# Ni-MH-charger-module.net
KiCad netlist of a schematic drawn in EAGLE
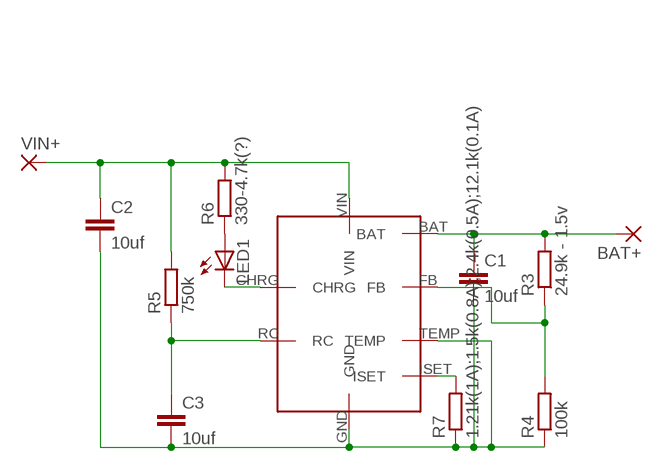
[diagram p0: schematic, sheet 1]

(export (version "E")
  (design (tool "Eeschema 10.0.6"))
  (components
    (comp (ref "BAT+")
      (value "SMD5")
      (footprint "eagle-import:SMD2,54-5,08")
      (libsource (lib "eagle-import") (part "SMD5"))
    )
    (comp (ref "C1")
      (value "10uf")
      (footprint "eagle-import:C0805")
      (libsource (lib "eagle-import") (part "C-EUC0805"))
    )
    (comp (ref "C2")
      (value "10uf")
      (footprint "eagle-import:C0805")
      (libsource (lib "eagle-import") (part "C-EUC0805"))
    )
    (comp (ref "C3")
      (value "10uf")
      (footprint "eagle-import:C0805")
      (libsource (lib "eagle-import") (part "C-EUC0805"))
    )
    (comp (ref "LED1")
      (value "LEDCHIPLED_0805")
      (footprint "eagle-import:CHIPLED_0805")
      (libsource (lib "eagle-import") (part "LEDCHIPLED_0805"))
    )
    (comp (ref "R3")
      (value "24.9k - 1.5v")
      (footprint "eagle-import:R0805")
      (libsource (lib "eagle-import") (part "R-EU_R0805"))
    )
    (comp (ref "R4")
      (value "100k")
      (footprint "eagle-import:R0805")
      (libsource (lib "eagle-import") (part "R-EU_R0805"))
    )
    (comp (ref "R5")
      (value "750k")
      (footprint "eagle-import:R0805")
      (libsource (lib "eagle-import") (part "R-EU_R0805"))
    )
    (comp (ref "R6")
      (value "330-4.7k(?)")
      (footprint "eagle-import:R0805")
      (libsource (lib "eagle-import") (part "R-EU_R0805"))
    )
    (comp (ref "R7")
      (value "1.21k(1A);1.5k(0.8A);2.4k(0.5A);12.1k(0.1A)")
      (footprint "eagle-import:R0805")
      (libsource (lib "eagle-import") (part "R-EU_R0805"))
    )
    (comp (ref "U$1")
      (value "CN3085")
      (footprint "eagle-import:CN3085")
      (libsource (lib "eagle-import") (part "CN3085"))
    )
    (comp (ref "VIN+")
      (value "SMD5")
      (footprint "eagle-import:SMD2,54-5,08")
      (libsource (lib "eagle-import") (part "SMD5"))
    )
  )
  (nets
    (net (code "1") (name "Net-(BAT+-P)") (class "Default")
      (node (ref "BAT+") (pin "1") (pinfunction "P_1") (pintype "passive"))
      (node (ref "C1") (pin "1") (pinfunction "1_1") (pintype "passive"))
      (node (ref "R3") (pin "2") (pinfunction "2_2") (pintype "passive"))
      (node (ref "U$1") (pin "BAT") (pinfunction "BAT_BAT") (pintype "bidirectional"))
    )
    (net (code "2") (name "Net-(C1-Pad2)") (class "Default")
      (node (ref "C1") (pin "2") (pinfunction "2_2") (pintype "passive"))
      (node (ref "C2") (pin "2") (pinfunction "2_2") (pintype "passive"))
      (node (ref "C3") (pin "2") (pinfunction "2_2") (pintype "passive"))
      (node (ref "R4") (pin "1") (pinfunction "1_1") (pintype "passive"))
      (node (ref "R7") (pin "1") (pinfunction "1_1") (pintype "passive"))
      (node (ref "U$1") (pin "GND") (pinfunction "GND_GND") (pintype "bidirectional"))
      (node (ref "U$1") (pin "TEMP") (pinfunction "TEMP_TEMP") (pintype "bidirectional"))
    )
    (net (code "3") (name "Net-(C3-Pad1)") (class "Default")
      (node (ref "C3") (pin "1") (pinfunction "1_1") (pintype "passive"))
      (node (ref "R5") (pin "1") (pinfunction "1_1") (pintype "passive"))
      (node (ref "U$1") (pin "RC") (pinfunction "RC_RC") (pintype "bidirectional"))
    )
    (net (code "4") (name "Net-(LED1-PadA)") (class "Default")
      (node (ref "LED1") (pin "A") (pinfunction "A_A") (pintype "passive"))
      (node (ref "R6") (pin "1") (pinfunction "1_1") (pintype "passive"))
    )
    (net (code "5") (name "Net-(LED1-PadC)") (class "Default")
      (node (ref "LED1") (pin "C") (pinfunction "C_C") (pintype "passive"))
      (node (ref "U$1") (pin "CHRG") (pinfunction "CHRG_CHRG") (pintype "bidirectional"))
    )
    (net (code "6") (name "Net-(R3-Pad1)") (class "Default")
      (node (ref "R3") (pin "1") (pinfunction "1_1") (pintype "passive"))
      (node (ref "R4") (pin "2") (pinfunction "2_2") (pintype "passive"))
      (node (ref "U$1") (pin "FB") (pinfunction "FB_FB") (pintype "bidirectional"))
    )
    (net (code "7") (name "Net-(R7-Pad2)") (class "Default")
      (node (ref "R7") (pin "2") (pinfunction "2_2") (pintype "passive"))
      (node (ref "U$1") (pin "ISET") (pinfunction "ISET_ISET") (pintype "bidirectional"))
    )
    (net (code "8") (name "Net-(VIN+-P)") (class "Default")
      (node (ref "C2") (pin "1") (pinfunction "1_1") (pintype "passive"))
      (node (ref "R5") (pin "2") (pinfunction "2_2") (pintype "passive"))
      (node (ref "R6") (pin "2") (pinfunction "2_2") (pintype "passive"))
      (node (ref "U$1") (pin "VIN") (pinfunction "VIN_VIN") (pintype "bidirectional"))
      (node (ref "VIN+") (pin "1") (pinfunction "P_1") (pintype "passive"))
    )
  )
)
